# SPEC_A7.net
KiCad netlist of a schematic drawn in Altium Designer
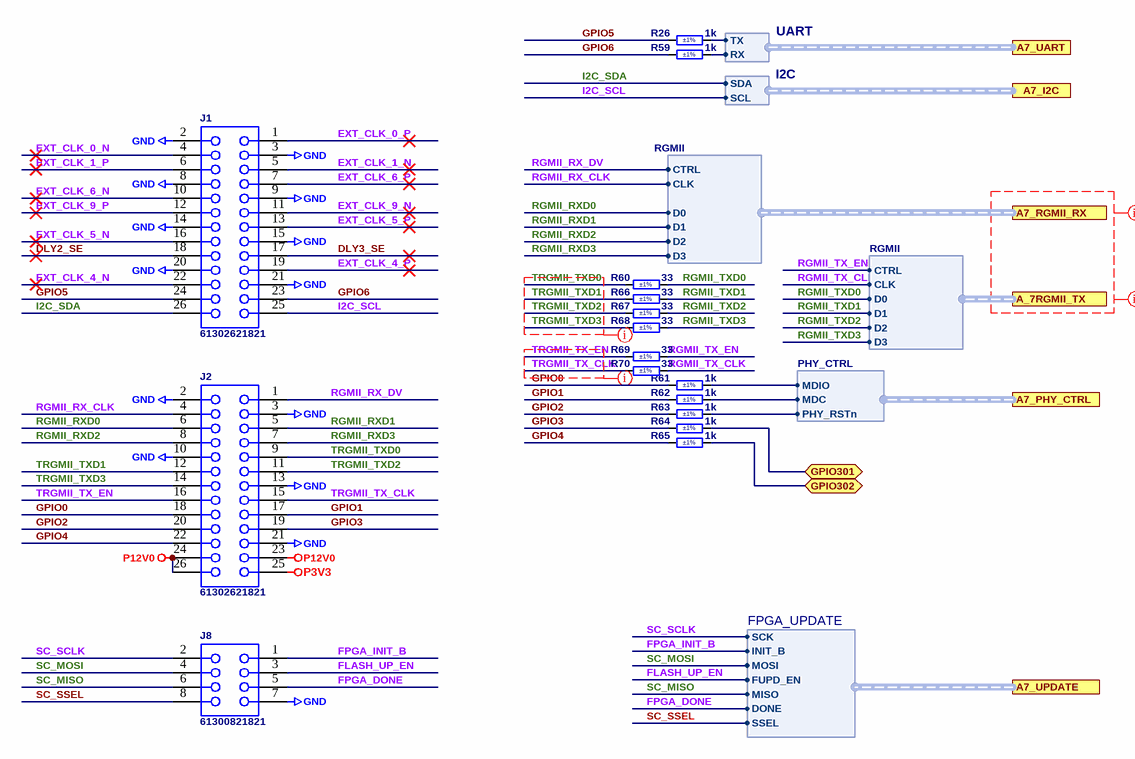
[diagram p0: SPEC_A7.SchDoc]

(export (version "E")
  (design (tool "Eeschema 10.0.6"))
  (components
    (comp (ref "J1")
      (value "61302621821")
      (footprint "61302621821")
      (description "WR-PHD Socket Header, THT, Vertical, pitch 2.54mm, 2 Row, 26P")
      (fields (field (name "MANUFACTURER") "Wurth Elektronik"))
      (libsource (lib "Altium_WR-PHD (rev24a)") (part "61302621821"))
    )
    (comp (ref "J2")
      (value "61302621821")
      (footprint "61302621821")
      (description "WR-PHD Socket Header, THT, Vertical, pitch 2.54mm, 2 Row, 26P")
      (fields (field (name "MANUFACTURER") "Wurth Elektronik"))
      (libsource (lib "Altium_WR-PHD (rev24a)") (part "61302621821"))
    )
    (comp (ref "J8")
      (value "61300821821")
      (footprint "61300821821")
      (description "WR-PHD Socket Header, THT, Vertical, pitch 2.54mm, 2 Row, 8P")
      (fields (field (name "MANUFACTURER") "Wurth Elektronik"))
      (libsource (lib "Altium_WR-PHD (rev24a)") (part "61300821821"))
    )
    (comp (ref "R26")
      (value "1k")
      (footprint "RESC1005X40N")
      (description "Resistor - 1%")
      (fields
        (field (name "TOLERANCE") "±1%")
        (field (name "PART NUMBER") "R0402_1K_1%_0.0625W_100PPM")
        (field (name "POWER") "0.0625W")
        (field (name "AUTHOR") "CERN DEM JLC")
      )
      (libsource (lib "Resistors") (part "Resistor - 1%"))
    )
    (comp (ref "R59")
      (value "1k")
      (footprint "RESC1005X40N")
      (description "Resistor - 1%")
      (fields
        (field (name "TOLERANCE") "±1%")
        (field (name "PART NUMBER") "R0402_1K_1%_0.0625W_100PPM")
        (field (name "POWER") "0.0625W")
        (field (name "AUTHOR") "CERN DEM JLC")
      )
      (libsource (lib "Resistors") (part "Resistor - 1%"))
    )
    (comp (ref "R60")
      (value "33")
      (footprint "RESC1005X40N")
      (description "Resistor - 1%")
      (fields
        (field (name "TOLERANCE") "±1%")
        (field (name "PART NUMBER") "R0402_33R_1%_0.0625W_100PPM")
        (field (name "POWER") "0.0625W")
        (field (name "AUTHOR") "CERN DEM JLC")
      )
      (libsource (lib "Resistors") (part "Resistor - 1%"))
    )
    (comp (ref "R61")
      (value "1k")
      (footprint "RESC1005X40N")
      (description "Resistor - 1%")
      (fields
        (field (name "TOLERANCE") "±1%")
        (field (name "PART NUMBER") "R0402_1K_1%_0.0625W_100PPM")
        (field (name "POWER") "0.0625W")
        (field (name "AUTHOR") "CERN DEM JLC")
      )
      (libsource (lib "Resistors") (part "Resistor - 1%"))
    )
    (comp (ref "R62")
      (value "1k")
      (footprint "RESC1005X40N")
      (description "Resistor - 1%")
      (fields
        (field (name "TOLERANCE") "±1%")
        (field (name "PART NUMBER") "R0402_1K_1%_0.0625W_100PPM")
        (field (name "POWER") "0.0625W")
        (field (name "AUTHOR") "CERN DEM JLC")
      )
      (libsource (lib "Resistors") (part "Resistor - 1%"))
    )
    (comp (ref "R63")
      (value "1k")
      (footprint "RESC1005X40N")
      (description "Resistor - 1%")
      (fields
        (field (name "TOLERANCE") "±1%")
        (field (name "PART NUMBER") "R0402_1K_1%_0.0625W_100PPM")
        (field (name "POWER") "0.0625W")
        (field (name "AUTHOR") "CERN DEM JLC")
      )
      (libsource (lib "Resistors") (part "Resistor - 1%"))
    )
    (comp (ref "R64")
      (value "1k")
      (footprint "RESC1005X40N")
      (description "Resistor - 1%")
      (fields
        (field (name "TOLERANCE") "±1%")
        (field (name "PART NUMBER") "R0402_1K_1%_0.0625W_100PPM")
        (field (name "POWER") "0.0625W")
        (field (name "AUTHOR") "CERN DEM JLC")
      )
      (libsource (lib "Resistors") (part "Resistor - 1%"))
    )
    (comp (ref "R65")
      (value "1k")
      (footprint "RESC1005X40N")
      (description "Resistor - 1%")
      (fields
        (field (name "TOLERANCE") "±1%")
        (field (name "PART NUMBER") "R0402_1K_1%_0.0625W_100PPM")
        (field (name "POWER") "0.0625W")
        (field (name "AUTHOR") "CERN DEM JLC")
      )
      (libsource (lib "Resistors") (part "Resistor - 1%"))
    )
    (comp (ref "R66")
      (value "33")
      (footprint "RESC1005X40N")
      (description "Resistor - 1%")
      (fields
        (field (name "TOLERANCE") "±1%")
        (field (name "PART NUMBER") "R0402_33R_1%_0.0625W_100PPM")
        (field (name "POWER") "0.0625W")
        (field (name "AUTHOR") "CERN DEM JLC")
      )
      (libsource (lib "Resistors") (part "Resistor - 1%"))
    )
    (comp (ref "R67")
      (value "33")
      (footprint "RESC1005X40N")
      (description "Resistor - 1%")
      (fields
        (field (name "TOLERANCE") "±1%")
        (field (name "PART NUMBER") "R0402_33R_1%_0.0625W_100PPM")
        (field (name "POWER") "0.0625W")
        (field (name "AUTHOR") "CERN DEM JLC")
      )
      (libsource (lib "Resistors") (part "Resistor - 1%"))
    )
    (comp (ref "R68")
      (value "33")
      (footprint "RESC1005X40N")
      (description "Resistor - 1%")
      (fields
        (field (name "TOLERANCE") "±1%")
        (field (name "PART NUMBER") "R0402_33R_1%_0.0625W_100PPM")
        (field (name "POWER") "0.0625W")
        (field (name "AUTHOR") "CERN DEM JLC")
      )
      (libsource (lib "Resistors") (part "Resistor - 1%"))
    )
    (comp (ref "R69")
      (value "33")
      (footprint "RESC1005X40N")
      (description "Resistor - 1%")
      (fields
        (field (name "TOLERANCE") "±1%")
        (field (name "PART NUMBER") "R0402_33R_1%_0.0625W_100PPM")
        (field (name "POWER") "0.0625W")
        (field (name "AUTHOR") "CERN DEM JLC")
      )
      (libsource (lib "Resistors") (part "Resistor - 1%"))
    )
    (comp (ref "R70")
      (value "33")
      (footprint "RESC1005X40N")
      (description "Resistor - 1%")
      (fields
        (field (name "TOLERANCE") "±1%")
        (field (name "PART NUMBER") "R0402_33R_1%_0.0625W_100PPM")
        (field (name "POWER") "0.0625W")
        (field (name "AUTHOR") "CERN DEM JLC")
      )
      (libsource (lib "Resistors") (part "Resistor - 1%"))
    )
  )
  (nets
    (net (code "7") (name "/DLY2_SE") (class "Default")
      (node (ref "J1") (pin "18") (pinfunction "18_18") (pintype "passive"))
    )
    (net (code "9") (name "/DLY3_SE") (class "Default")
      (node (ref "J1") (pin "17") (pinfunction "17_17") (pintype "passive"))
    )
    (net (code "10") (name "/EXT_CLK_0_N") (class "Default")
      (node (ref "J1") (pin "4") (pinfunction "4_4") (pintype "passive"))
    )
    (net (code "13") (name "/EXT_CLK_0_P") (class "Default")
      (node (ref "J1") (pin "1") (pinfunction "1_1") (pintype "passive"))
    )
    (net (code "15") (name "/EXT_CLK_1_N") (class "Default")
      (node (ref "J1") (pin "5") (pinfunction "5_5") (pintype "passive"))
    )
    (net (code "17") (name "/EXT_CLK_1_P") (class "Default")
      (node (ref "J1") (pin "6") (pinfunction "6_6") (pintype "passive"))
    )
    (net (code "18") (name "/EXT_CLK_4_N") (class "Default")
      (node (ref "J1") (pin "22") (pinfunction "22_22") (pintype "passive"))
    )
    (net (code "20") (name "/EXT_CLK_4_P") (class "Default")
      (node (ref "J1") (pin "19") (pinfunction "19_19") (pintype "passive"))
    )
    (net (code "21") (name "/EXT_CLK_5_N") (class "Default")
      (node (ref "J1") (pin "16") (pinfunction "16_16") (pintype "passive"))
    )
    (net (code "22") (name "/EXT_CLK_5_P") (class "Default")
      (node (ref "J1") (pin "13") (pinfunction "13_13") (pintype "passive"))
    )
    (net (code "23") (name "/EXT_CLK_6_N") (class "Default")
      (node (ref "J1") (pin "10") (pinfunction "10_10") (pintype "passive"))
    )
    (net (code "24") (name "/EXT_CLK_6_P") (class "Default")
      (node (ref "J1") (pin "7") (pinfunction "7_7") (pintype "passive"))
    )
    (net (code "25") (name "/EXT_CLK_9_N") (class "Default")
      (node (ref "J1") (pin "11") (pinfunction "11_11") (pintype "passive"))
    )
    (net (code "26") (name "/EXT_CLK_9_P") (class "Default")
      (node (ref "J1") (pin "12") (pinfunction "12_12") (pintype "passive"))
    )
    (net (code "27") (name "/FLASH_UP_EN") (class "Default")
      (node (ref "J8") (pin "3") (pinfunction "3_3") (pintype "passive"))
    )
    (net (code "28") (name "/FPGA_DONE") (class "Default")
      (node (ref "J8") (pin "5") (pinfunction "5_5") (pintype "passive"))
    )
    (net (code "29") (name "/FPGA_INIT_B") (class "Default")
      (node (ref "J8") (pin "1") (pinfunction "1_1") (pintype "passive"))
    )
    (net (code "30") (name "/GPIO0") (class "Default")
      (node (ref "J2") (pin "18") (pinfunction "18_18") (pintype "passive"))
      (node (ref "R61") (pin "1") (pinfunction "1_1") (pintype "passive"))
    )
    (net (code "31") (name "/GPIO1") (class "Default")
      (node (ref "J2") (pin "17") (pinfunction "17_17") (pintype "passive"))
      (node (ref "R62") (pin "1") (pinfunction "1_1") (pintype "passive"))
    )
    (net (code "32") (name "/GPIO2") (class "Default")
      (node (ref "J2") (pin "20") (pinfunction "20_20") (pintype "passive"))
      (node (ref "R63") (pin "1") (pinfunction "1_1") (pintype "passive"))
    )
    (net (code "33") (name "/GPIO3") (class "Default")
      (node (ref "J2") (pin "19") (pinfunction "19_19") (pintype "passive"))
      (node (ref "R64") (pin "1") (pinfunction "1_1") (pintype "passive"))
    )
    (net (code "34") (name "/GPIO4") (class "Default")
      (node (ref "J2") (pin "22") (pinfunction "22_22") (pintype "passive"))
      (node (ref "R65") (pin "1") (pinfunction "1_1") (pintype "passive"))
    )
    (net (code "35") (name "/GPIO5") (class "Default")
      (node (ref "J1") (pin "24") (pinfunction "24_24") (pintype "passive"))
      (node (ref "R26") (pin "1") (pinfunction "1_1") (pintype "passive"))
    )
    (net (code "36") (name "/GPIO6") (class "Default")
      (node (ref "J1") (pin "23") (pinfunction "23_23") (pintype "passive"))
      (node (ref "R59") (pin "1") (pinfunction "1_1") (pintype "passive"))
    )
    (net (code "37") (name "/GPIO301") (class "Default")
      (node (ref "R64") (pin "2") (pinfunction "2_2") (pintype "passive"))
    )
    (net (code "38") (name "/GPIO302") (class "Default")
      (node (ref "R65") (pin "2") (pinfunction "2_2") (pintype "passive"))
    )
    (net (code "39") (name "/I2C_SCL") (class "Default")
      (node (ref "J1") (pin "25") (pinfunction "25_25") (pintype "passive"))
    )
    (net (code "40") (name "/I2C_SDA") (class "Default")
      (node (ref "J1") (pin "26") (pinfunction "26_26") (pintype "passive"))
    )
    (net (code "41") (name "/MDC") (class "Default")
      (node (ref "R62") (pin "2") (pinfunction "2_2") (pintype "passive"))
    )
    (net (code "42") (name "/MDIO") (class "Default")
      (node (ref "R61") (pin "2") (pinfunction "2_2") (pintype "passive"))
    )
    (net (code "43") (name "/PHY_RSTn") (class "Default")
      (node (ref "R63") (pin "2") (pinfunction "2_2") (pintype "passive"))
    )
    (net (code "44") (name "/RGMII_RXD0") (class "Default")
      (node (ref "J2") (pin "6") (pinfunction "6_6") (pintype "passive"))
    )
    (net (code "45") (name "/RGMII_RXD1") (class "Default")
      (node (ref "J2") (pin "5") (pinfunction "5_5") (pintype "passive"))
    )
    (net (code "46") (name "/RGMII_RXD2") (class "Default")
      (node (ref "J2") (pin "8") (pinfunction "8_8") (pintype "passive"))
    )
    (net (code "47") (name "/RGMII_RXD3") (class "Default")
      (node (ref "J2") (pin "7") (pinfunction "7_7") (pintype "passive"))
    )
    (net (code "48") (name "/RGMII_RX_CLK") (class "Default")
      (node (ref "J2") (pin "4") (pinfunction "4_4") (pintype "passive"))
    )
    (net (code "49") (name "/RGMII_RX_DV") (class "Default")
      (node (ref "J2") (pin "1") (pinfunction "1_1") (pintype "passive"))
    )
    (net (code "50") (name "/RGMII_TXD0") (class "Default")
      (node (ref "R60") (pin "2") (pinfunction "2_2") (pintype "passive"))
    )
    (net (code "51") (name "/RGMII_TXD1") (class "Default")
      (node (ref "R66") (pin "2") (pinfunction "2_2") (pintype "passive"))
    )
    (net (code "52") (name "/RGMII_TXD2") (class "Default")
      (node (ref "R67") (pin "2") (pinfunction "2_2") (pintype "passive"))
    )
    (net (code "53") (name "/RGMII_TXD3") (class "Default")
      (node (ref "R68") (pin "2") (pinfunction "2_2") (pintype "passive"))
    )
    (net (code "54") (name "/RGMII_TX_CLK") (class "Default")
      (node (ref "R70") (pin "2") (pinfunction "2_2") (pintype "passive"))
    )
    (net (code "55") (name "/RGMII_TX_EN") (class "Default")
      (node (ref "R69") (pin "2") (pinfunction "2_2") (pintype "passive"))
    )
    (net (code "56") (name "/RX") (class "Default")
      (node (ref "R59") (pin "2") (pinfunction "2_2") (pintype "passive"))
    )
    (net (code "57") (name "/SC_MISO") (class "Default")
      (node (ref "J8") (pin "6") (pinfunction "6_6") (pintype "passive"))
    )
    (net (code "58") (name "/SC_MOSI") (class "Default")
      (node (ref "J8") (pin "4") (pinfunction "4_4") (pintype "passive"))
    )
    (net (code "59") (name "/SC_SCLK") (class "Default")
      (node (ref "J8") (pin "2") (pinfunction "2_2") (pintype "passive"))
    )
    (net (code "60") (name "/SC_SSEL") (class "Default")
      (node (ref "J8") (pin "8") (pinfunction "8_8") (pintype "passive"))
    )
    (net (code "66") (name "/TRGMII_TXD0") (class "Default")
      (node (ref "J2") (pin "9") (pinfunction "9_9") (pintype "passive"))
      (node (ref "R60") (pin "1") (pinfunction "1_1") (pintype "passive"))
    )
    (net (code "67") (name "/TRGMII_TXD1") (class "Default")
      (node (ref "J2") (pin "12") (pinfunction "12_12") (pintype "passive"))
      (node (ref "R66") (pin "1") (pinfunction "1_1") (pintype "passive"))
    )
    (net (code "68") (name "/TRGMII_TXD2") (class "Default")
      (node (ref "J2") (pin "11") (pinfunction "11_11") (pintype "passive"))
      (node (ref "R67") (pin "1") (pinfunction "1_1") (pintype "passive"))
    )
    (net (code "69") (name "/TRGMII_TXD3") (class "Default")
      (node (ref "J2") (pin "14") (pinfunction "14_14") (pintype "passive"))
      (node (ref "R68") (pin "1") (pinfunction "1_1") (pintype "passive"))
    )
    (net (code "70") (name "/TRGMII_TX_CLK") (class "Default")
      (node (ref "J2") (pin "15") (pinfunction "15_15") (pintype "passive"))
      (node (ref "R70") (pin "1") (pinfunction "1_1") (pintype "passive"))
    )
    (net (code "71") (name "/TRGMII_TX_EN") (class "Default")
      (node (ref "J2") (pin "16") (pinfunction "16_16") (pintype "passive"))
      (node (ref "R69") (pin "1") (pinfunction "1_1") (pintype "passive"))
    )
    (net (code "72") (name "/TX") (class "Default")
      (node (ref "R26") (pin "2") (pinfunction "2_2") (pintype "passive"))
    )
    (net (code "73") (name "GND") (class "Default")
      (node (ref "J1") (pin "14") (pinfunction "14_14") (pintype "passive"))
      (node (ref "J1") (pin "15") (pinfunction "15_15") (pintype "passive"))
      (node (ref "J1") (pin "2") (pinfunction "2_2") (pintype "passive"))
      (node (ref "J1") (pin "20") (pinfunction "20_20") (pintype "passive"))
      (node (ref "J1") (pin "21") (pinfunction "21_21") (pintype "passive"))
      (node (ref "J1") (pin "3") (pinfunction "3_3") (pintype "passive"))
      (node (ref "J1") (pin "8") (pinfunction "8_8") (pintype "passive"))
      (node (ref "J1") (pin "9") (pinfunction "9_9") (pintype "passive"))
      (node (ref "J2") (pin "10") (pinfunction "10_10") (pintype "passive"))
      (node (ref "J2") (pin "13") (pinfunction "13_13") (pintype "passive"))
      (node (ref "J2") (pin "2") (pinfunction "2_2") (pintype "passive"))
      (node (ref "J2") (pin "21") (pinfunction "21_21") (pintype "passive"))
      (node (ref "J2") (pin "3") (pinfunction "3_3") (pintype "passive"))
      (node (ref "J8") (pin "7") (pinfunction "7_7") (pintype "passive"))
    )
    (net (code "74") (name "P3V3") (class "Default")
      (node (ref "J2") (pin "25") (pinfunction "25_25") (pintype "passive"))
    )
    (net (code "75") (name "P12V0") (class "Default")
      (node (ref "J2") (pin "23") (pinfunction "23_23") (pintype "passive"))
      (node (ref "J2") (pin "24") (pinfunction "24_24") (pintype "passive"))
      (node (ref "J2") (pin "26") (pinfunction "26_26") (pintype "passive"))
    )
  )
)
